# Power_Clock.net
KiCad netlist of a schematic drawn in Altium Designer
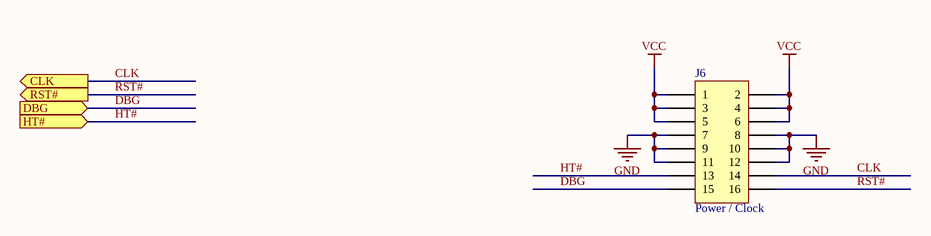
[diagram p0: Power_Clock.SchDoc]

(export (version "E")
  (design (tool "Eeschema 10.0.6"))
  (components
    (comp (ref "J6")
      (value "Power / Clock")
      (footprint "HDR2X8")
      (description "Header, 8-Pin, Dual row")
      (fields (field (name "PUBLISHER") "Altium Limited"))
      (libsource (lib "Miscellaneous Connectors") (part "Header 8X2"))
    )
  )
  (nets
    (net (code "1") (name "/CLK") (class "Default")
      (node (ref "J6") (pin "14") (pinfunction "14_14") (pintype "passive"))
    )
    (net (code "2") (name "/DBG") (class "Default")
      (node (ref "J6") (pin "15") (pinfunction "15_15") (pintype "passive"))
    )
    (net (code "3") (name "/HT#") (class "Default")
      (node (ref "J6") (pin "13") (pinfunction "13_13") (pintype "passive"))
    )
    (net (code "4") (name "/RST#") (class "Default")
      (node (ref "J6") (pin "16") (pinfunction "16_16") (pintype "passive"))
    )
    (net (code "5") (name "GND") (class "Default")
      (node (ref "J6") (pin "10") (pinfunction "10_10") (pintype "passive"))
      (node (ref "J6") (pin "11") (pinfunction "11_11") (pintype "passive"))
      (node (ref "J6") (pin "12") (pinfunction "12_12") (pintype "passive"))
      (node (ref "J6") (pin "7") (pinfunction "7_7") (pintype "passive"))
      (node (ref "J6") (pin "8") (pinfunction "8_8") (pintype "passive"))
      (node (ref "J6") (pin "9") (pinfunction "9_9") (pintype "passive"))
    )
    (net (code "6") (name "VCC") (class "Default")
      (node (ref "J6") (pin "1") (pinfunction "1_1") (pintype "passive"))
      (node (ref "J6") (pin "2") (pinfunction "2_2") (pintype "passive"))
      (node (ref "J6") (pin "3") (pinfunction "3_3") (pintype "passive"))
      (node (ref "J6") (pin "4") (pinfunction "4_4") (pintype "passive"))
      (node (ref "J6") (pin "5") (pinfunction "5_5") (pintype "passive"))
      (node (ref "J6") (pin "6") (pinfunction "6_6") (pintype "passive"))
    )
  )
)
